# filter-prototype.net
KiCad netlist of a schematic drawn in EAGLE
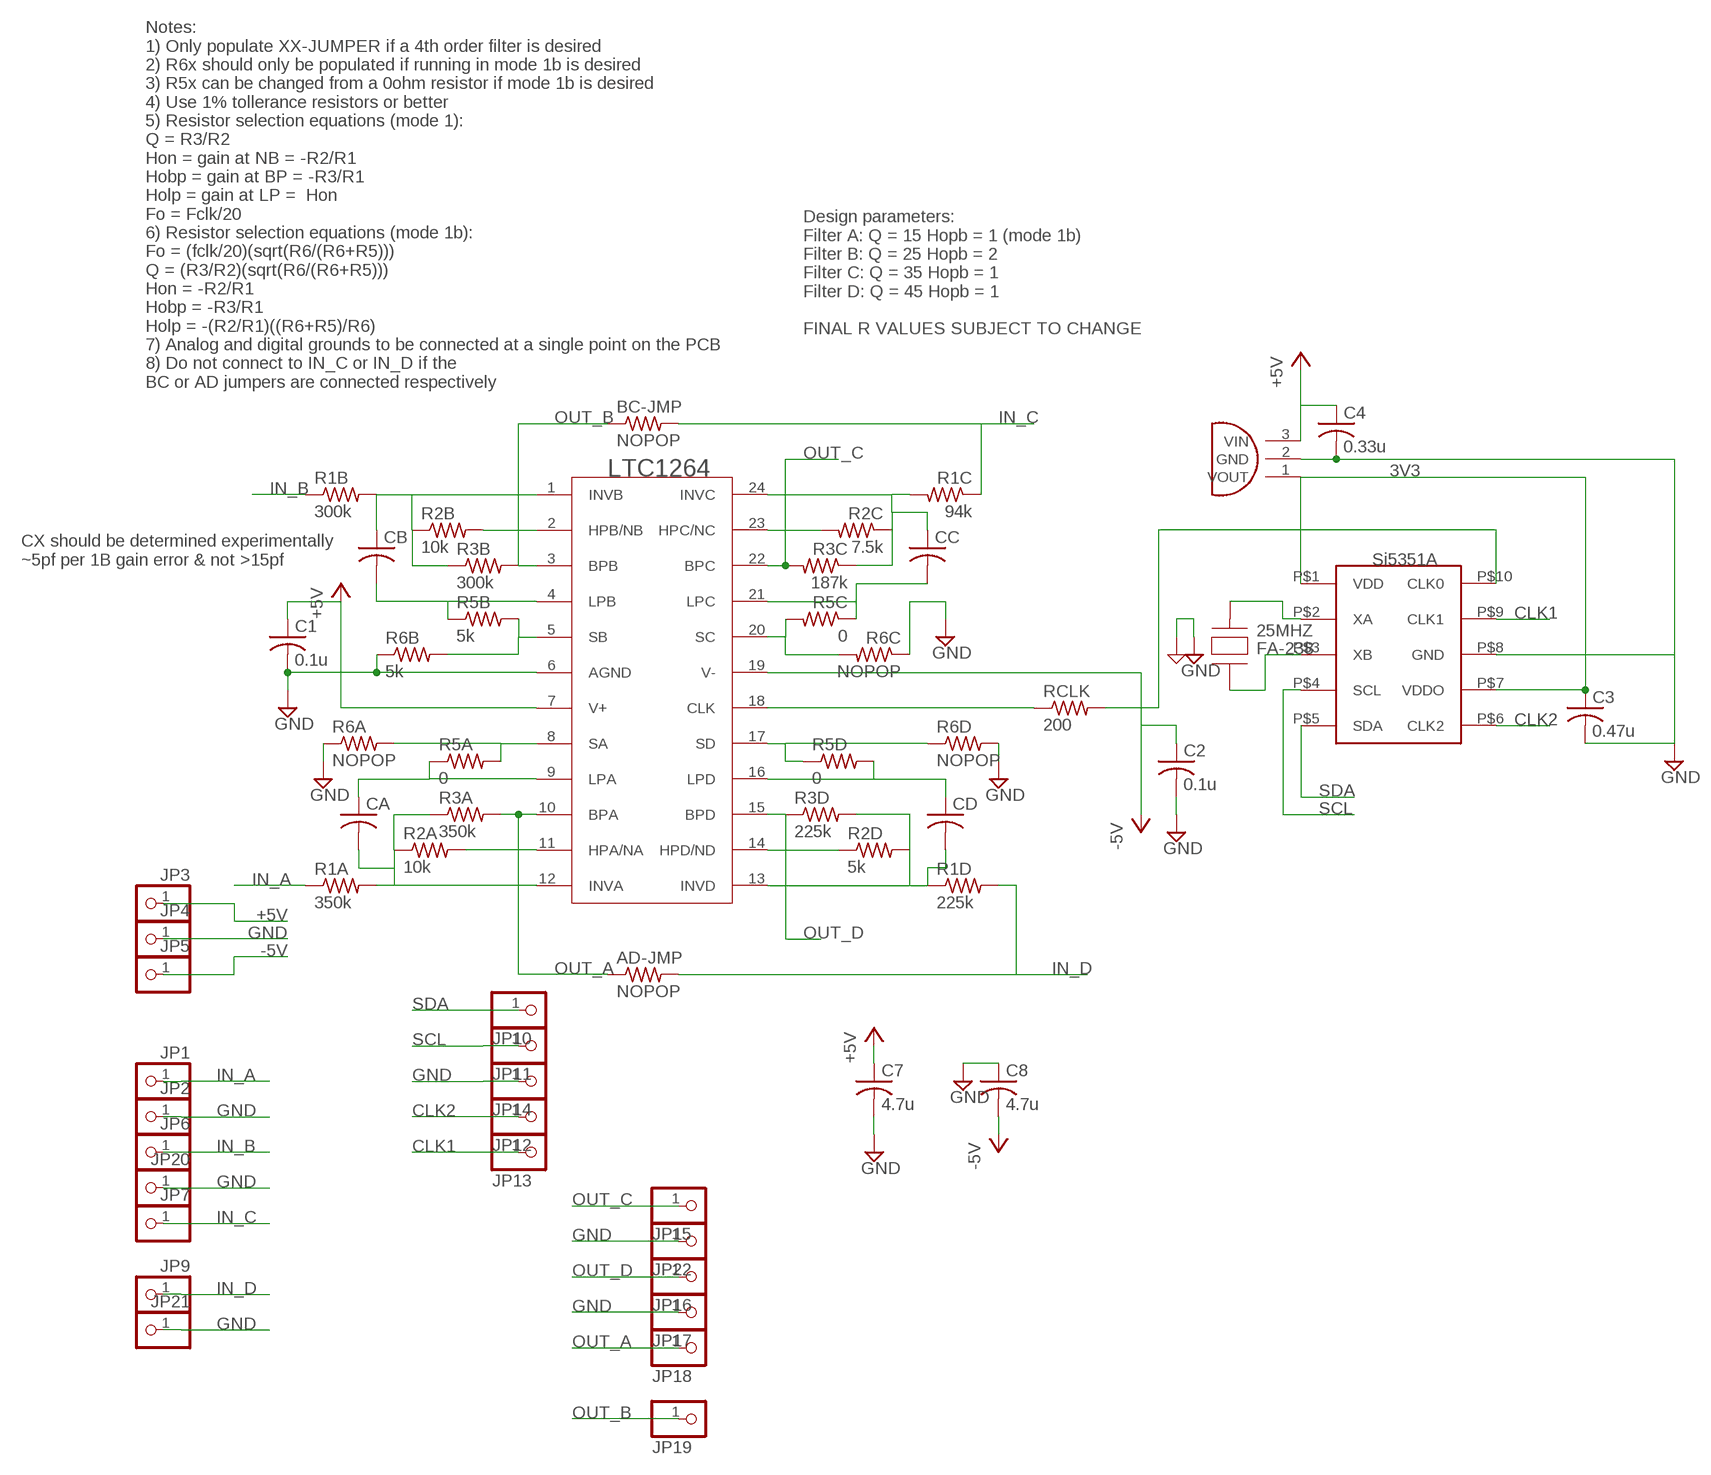
[diagram p0: schematic, sheet 1]

(export (version "E")
  (design (tool "Eeschema 10.0.6"))
  (components
    (comp (ref "25MHZ")
      (value "FA-238")
      (footprint "eagle-import:FA-238")
      (libsource (lib "eagle-import") (part "FA-238"))
    )
    (comp (ref "AD-JMP")
      (value "NOPOP")
      (footprint "eagle-import:R0805")
      (libsource (lib "eagle-import") (part "R-US_R0805"))
    )
    (comp (ref "BC-JMP")
      (value "NOPOP")
      (footprint "eagle-import:R0805")
      (libsource (lib "eagle-import") (part "R-US_R0805"))
    )
    (comp (ref "C1")
      (value "0.1u")
      (footprint "eagle-import:C0805")
      (libsource (lib "eagle-import") (part "C-USC0805"))
    )
    (comp (ref "C2")
      (value "0.1u")
      (footprint "eagle-import:C0805")
      (libsource (lib "eagle-import") (part "C-USC0805"))
    )
    (comp (ref "C3")
      (value "0.47u")
      (footprint "eagle-import:C0805")
      (libsource (lib "eagle-import") (part "C-USC0805"))
    )
    (comp (ref "C4")
      (value "0.33u")
      (footprint "eagle-import:C0805")
      (libsource (lib "eagle-import") (part "C-USC0805"))
    )
    (comp (ref "C7")
      (value "4.7u")
      (footprint "eagle-import:C0805")
      (libsource (lib "eagle-import") (part "C-USC0805"))
    )
    (comp (ref "C8")
      (value "4.7u")
      (footprint "eagle-import:C0805")
      (libsource (lib "eagle-import") (part "C-USC0805"))
    )
    (comp (ref "CA")
      (value "C-USC0805")
      (footprint "eagle-import:C0805")
      (libsource (lib "eagle-import") (part "C-USC0805"))
    )
    (comp (ref "CB")
      (value "C-USC0805")
      (footprint "eagle-import:C0805")
      (libsource (lib "eagle-import") (part "C-USC0805"))
    )
    (comp (ref "CC")
      (value "C-USC0805")
      (footprint "eagle-import:C0805")
      (libsource (lib "eagle-import") (part "C-USC0805"))
    )
    (comp (ref "CD")
      (value "C-USC0805")
      (footprint "eagle-import:C0805")
      (libsource (lib "eagle-import") (part "C-USC0805"))
    )
    (comp (ref "JP1")
      (value "PINHD-1X1")
      (footprint "eagle-import:1X01")
      (libsource (lib "eagle-import") (part "PINHD-1X1"))
    )
    (comp (ref "JP2")
      (value "PINHD-1X1")
      (footprint "eagle-import:1X01")
      (libsource (lib "eagle-import") (part "PINHD-1X1"))
    )
    (comp (ref "JP3")
      (value "PINHD-1X1")
      (footprint "eagle-import:1X01")
      (libsource (lib "eagle-import") (part "PINHD-1X1"))
    )
    (comp (ref "JP4")
      (value "PINHD-1X1")
      (footprint "eagle-import:1X01")
      (libsource (lib "eagle-import") (part "PINHD-1X1"))
    )
    (comp (ref "JP5")
      (value "PINHD-1X1")
      (footprint "eagle-import:1X01")
      (libsource (lib "eagle-import") (part "PINHD-1X1"))
    )
    (comp (ref "JP6")
      (value "PINHD-1X1")
      (footprint "eagle-import:1X01")
      (libsource (lib "eagle-import") (part "PINHD-1X1"))
    )
    (comp (ref "JP7")
      (value "PINHD-1X1")
      (footprint "eagle-import:1X01")
      (libsource (lib "eagle-import") (part "PINHD-1X1"))
    )
    (comp (ref "JP9")
      (value "PINHD-1X1")
      (footprint "eagle-import:1X01")
      (libsource (lib "eagle-import") (part "PINHD-1X1"))
    )
    (comp (ref "JP10")
      (value "PINHD-1X1")
      (footprint "eagle-import:1X01")
      (libsource (lib "eagle-import") (part "PINHD-1X1"))
    )
    (comp (ref "JP11")
      (value "PINHD-1X1")
      (footprint "eagle-import:1X01")
      (libsource (lib "eagle-import") (part "PINHD-1X1"))
    )
    (comp (ref "JP12")
      (value "PINHD-1X1")
      (footprint "eagle-import:1X01")
      (libsource (lib "eagle-import") (part "PINHD-1X1"))
    )
    (comp (ref "JP13")
      (value "PINHD-1X1")
      (footprint "eagle-import:1X01")
      (libsource (lib "eagle-import") (part "PINHD-1X1"))
    )
    (comp (ref "JP14")
      (value "PINHD-1X1")
      (footprint "eagle-import:1X01")
      (libsource (lib "eagle-import") (part "PINHD-1X1"))
    )
    (comp (ref "JP15")
      (value "PINHD-1X1")
      (footprint "eagle-import:1X01")
      (libsource (lib "eagle-import") (part "PINHD-1X1"))
    )
    (comp (ref "JP16")
      (value "PINHD-1X1")
      (footprint "eagle-import:1X01")
      (libsource (lib "eagle-import") (part "PINHD-1X1"))
    )
    (comp (ref "JP17")
      (value "PINHD-1X1")
      (footprint "eagle-import:1X01")
      (libsource (lib "eagle-import") (part "PINHD-1X1"))
    )
    (comp (ref "JP18")
      (value "PINHD-1X1")
      (footprint "eagle-import:1X01")
      (libsource (lib "eagle-import") (part "PINHD-1X1"))
    )
    (comp (ref "JP19")
      (value "PINHD-1X1")
      (footprint "eagle-import:1X01")
      (libsource (lib "eagle-import") (part "PINHD-1X1"))
    )
    (comp (ref "JP20")
      (value "PINHD-1X1")
      (footprint "eagle-import:1X01")
      (libsource (lib "eagle-import") (part "PINHD-1X1"))
    )
    (comp (ref "JP21")
      (value "PINHD-1X1")
      (footprint "eagle-import:1X01")
      (libsource (lib "eagle-import") (part "PINHD-1X1"))
    )
    (comp (ref "JP22")
      (value "PINHD-1X1")
      (footprint "eagle-import:1X01")
      (libsource (lib "eagle-import") (part "PINHD-1X1"))
    )
    (comp (ref "R1A")
      (value "350k")
      (footprint "eagle-import:R0805")
      (libsource (lib "eagle-import") (part "R-US_R0805"))
    )
    (comp (ref "R1B")
      (value "300k")
      (footprint "eagle-import:R0805")
      (libsource (lib "eagle-import") (part "R-US_R0805"))
    )
    (comp (ref "R1C")
      (value "94k")
      (footprint "eagle-import:R0805")
      (libsource (lib "eagle-import") (part "R-US_R0805"))
    )
    (comp (ref "R1D")
      (value "225k")
      (footprint "eagle-import:R0805")
      (libsource (lib "eagle-import") (part "R-US_R0805"))
    )
    (comp (ref "R2A")
      (value "10k")
      (footprint "eagle-import:R0805")
      (libsource (lib "eagle-import") (part "R-US_R0805"))
    )
    (comp (ref "R2B")
      (value "10k")
      (footprint "eagle-import:R0805")
      (libsource (lib "eagle-import") (part "R-US_R0805"))
    )
    (comp (ref "R2C")
      (value "7.5k")
      (footprint "eagle-import:R0805")
      (libsource (lib "eagle-import") (part "R-US_R0805"))
    )
    (comp (ref "R2D")
      (value "5k")
      (footprint "eagle-import:R0805")
      (libsource (lib "eagle-import") (part "R-US_R0805"))
    )
    (comp (ref "R3A")
      (value "350k")
      (footprint "eagle-import:R0805")
      (libsource (lib "eagle-import") (part "R-US_R0805"))
    )
    (comp (ref "R3B")
      (value "300k")
      (footprint "eagle-import:R0805")
      (libsource (lib "eagle-import") (part "R-US_R0805"))
    )
    (comp (ref "R3C")
      (value "187k")
      (footprint "eagle-import:R0805")
      (libsource (lib "eagle-import") (part "R-US_R0805"))
    )
    (comp (ref "R3D")
      (value "225k")
      (footprint "eagle-import:R0805")
      (libsource (lib "eagle-import") (part "R-US_R0805"))
    )
    (comp (ref "R5A")
      (value "0")
      (footprint "eagle-import:R0805")
      (libsource (lib "eagle-import") (part "R-US_R0805"))
    )
    (comp (ref "R5B")
      (value "5k")
      (footprint "eagle-import:R0805")
      (libsource (lib "eagle-import") (part "R-US_R0805"))
    )
    (comp (ref "R5C")
      (value "0")
      (footprint "eagle-import:R0805")
      (libsource (lib "eagle-import") (part "R-US_R0805"))
    )
    (comp (ref "R5D")
      (value "0")
      (footprint "eagle-import:R0805")
      (libsource (lib "eagle-import") (part "R-US_R0805"))
    )
    (comp (ref "R6A")
      (value "NOPOP")
      (footprint "eagle-import:R0805")
      (libsource (lib "eagle-import") (part "R-US_R0805"))
    )
    (comp (ref "R6B")
      (value "5k")
      (footprint "eagle-import:R0805")
      (libsource (lib "eagle-import") (part "R-US_R0805"))
    )
    (comp (ref "R6C")
      (value "NOPOP")
      (footprint "eagle-import:R0805")
      (libsource (lib "eagle-import") (part "R-US_R0805"))
    )
    (comp (ref "R6D")
      (value "NOPOP")
      (footprint "eagle-import:R0805")
      (libsource (lib "eagle-import") (part "R-US_R0805"))
    )
    (comp (ref "RCLK")
      (value "200")
      (footprint "eagle-import:R0805")
      (libsource (lib "eagle-import") (part "R-US_R0805"))
    )
    (comp (ref "U$1")
      (value "LTC1264SMD")
      (footprint "eagle-import:SO24W")
      (libsource (lib "eagle-import") (part "LTC1264SMD"))
    )
    (comp (ref "U$2")
      (value "SI5351A")
      (footprint "eagle-import:MSOP-10")
      (libsource (lib "eagle-import") (part "SI5351A"))
    )
    (comp (ref "U$3")
      (value "L78L33ACZ")
      (footprint "eagle-import:TO-92")
      (libsource (lib "eagle-import") (part "L78L33ACZ"))
    )
  )
  (nets
    (net (code "1") (name "+5V") (class "Default")
      (node (ref "C1") (pin "1") (pinfunction "1_1") (pintype "passive"))
      (node (ref "C4") (pin "1") (pinfunction "1_1") (pintype "passive"))
      (node (ref "C7") (pin "1") (pinfunction "1_1") (pintype "passive"))
      (node (ref "JP3") (pin "1") (pinfunction "1_1") (pintype "passive"))
      (node (ref "U$1") (pin "7") (pinfunction "V+_7") (pintype "bidirectional"))
      (node (ref "U$3") (pin "3") (pinfunction "VIN_3") (pintype "bidirectional"))
    )
    (net (code "2") (name "-5V") (class "Default")
      (node (ref "C2") (pin "1") (pinfunction "1_1") (pintype "passive"))
      (node (ref "C8") (pin "2") (pinfunction "2_2") (pintype "passive"))
      (node (ref "JP5") (pin "1") (pinfunction "1_1") (pintype "passive"))
      (node (ref "U$1") (pin "19") (pinfunction "V-_19") (pintype "bidirectional"))
    )
    (net (code "3") (name "/3V3") (class "Default")
      (node (ref "C3") (pin "1") (pinfunction "1_1") (pintype "passive"))
      (node (ref "U$2") (pin "P$1") (pinfunction "VDD_P$1") (pintype "bidirectional"))
      (node (ref "U$2") (pin "P$7") (pinfunction "VDDO_P$7") (pintype "bidirectional"))
      (node (ref "U$3") (pin "1") (pinfunction "VOUT_1") (pintype "bidirectional"))
    )
    (net (code "4") (name "/CLK1") (class "Default")
      (node (ref "JP13") (pin "1") (pinfunction "1_1") (pintype "passive"))
      (node (ref "U$2") (pin "P$9") (pinfunction "CLK1_P$9") (pintype "bidirectional"))
    )
    (net (code "5") (name "/CLK2") (class "Default")
      (node (ref "JP12") (pin "1") (pinfunction "1_1") (pintype "passive"))
      (node (ref "U$2") (pin "P$6") (pinfunction "CLK2_P$6") (pintype "bidirectional"))
    )
    (net (code "6") (name "/IN_A") (class "Default")
      (node (ref "JP1") (pin "1") (pinfunction "1_1") (pintype "passive"))
      (node (ref "R1A") (pin "1") (pinfunction "1_1") (pintype "passive"))
    )
    (net (code "7") (name "/IN_B") (class "Default")
      (node (ref "JP6") (pin "1") (pinfunction "1_1") (pintype "passive"))
      (node (ref "R1B") (pin "1") (pinfunction "1_1") (pintype "passive"))
    )
    (net (code "8") (name "/IN_C") (class "Default")
      (node (ref "BC-JMP") (pin "2") (pinfunction "2_2") (pintype "passive"))
      (node (ref "JP7") (pin "1") (pinfunction "1_1") (pintype "passive"))
      (node (ref "R1C") (pin "1") (pinfunction "1_1") (pintype "passive"))
    )
    (net (code "9") (name "/IN_D") (class "Default")
      (node (ref "AD-JMP") (pin "2") (pinfunction "2_2") (pintype "passive"))
      (node (ref "JP9") (pin "1") (pinfunction "1_1") (pintype "passive"))
      (node (ref "R1D") (pin "2") (pinfunction "2_2") (pintype "passive"))
    )
    (net (code "10") (name "/OUT_A") (class "Default")
      (node (ref "AD-JMP") (pin "1") (pinfunction "1_1") (pintype "passive"))
      (node (ref "JP18") (pin "1") (pinfunction "1_1") (pintype "passive"))
      (node (ref "R3A") (pin "2") (pinfunction "2_2") (pintype "passive"))
      (node (ref "U$1") (pin "10") (pinfunction "BPA_10") (pintype "bidirectional"))
    )
    (net (code "11") (name "/OUT_B") (class "Default")
      (node (ref "BC-JMP") (pin "1") (pinfunction "1_1") (pintype "passive"))
      (node (ref "JP19") (pin "1") (pinfunction "1_1") (pintype "passive"))
      (node (ref "R3B") (pin "2") (pinfunction "2_2") (pintype "passive"))
      (node (ref "U$1") (pin "3") (pinfunction "BPB_3") (pintype "bidirectional"))
    )
    (net (code "12") (name "/OUT_C") (class "Default")
      (node (ref "JP15") (pin "1") (pinfunction "1_1") (pintype "passive"))
      (node (ref "R3C") (pin "2") (pinfunction "2_2") (pintype "passive"))
      (node (ref "U$1") (pin "22") (pinfunction "BPC_22") (pintype "bidirectional"))
    )
    (net (code "13") (name "/OUT_D") (class "Default")
      (node (ref "JP16") (pin "1") (pinfunction "1_1") (pintype "passive"))
      (node (ref "R3D") (pin "1") (pinfunction "1_1") (pintype "passive"))
      (node (ref "U$1") (pin "15") (pinfunction "BPD_15") (pintype "bidirectional"))
    )
    (net (code "14") (name "/SCL") (class "Default")
      (node (ref "JP11") (pin "1") (pinfunction "1_1") (pintype "passive"))
      (node (ref "U$2") (pin "P$4") (pinfunction "SCL_P$4") (pintype "bidirectional"))
    )
    (net (code "15") (name "/SDA") (class "Default")
      (node (ref "JP10") (pin "1") (pinfunction "1_1") (pintype "passive"))
      (node (ref "U$2") (pin "P$5") (pinfunction "SDA_P$5") (pintype "bidirectional"))
    )
    (net (code "16") (name "GND") (class "Default")
      (node (ref "25MHZ") (pin "P$1") (pinfunction "GND_P$1") (pintype "bidirectional"))
      (node (ref "25MHZ") (pin "P$3") (pinfunction "GND_P$3") (pintype "bidirectional"))
      (node (ref "C1") (pin "2") (pinfunction "2_2") (pintype "passive"))
      (node (ref "C2") (pin "2") (pinfunction "2_2") (pintype "passive"))
      (node (ref "C3") (pin "2") (pinfunction "2_2") (pintype "passive"))
      (node (ref "C4") (pin "2") (pinfunction "2_2") (pintype "passive"))
      (node (ref "C7") (pin "2") (pinfunction "2_2") (pintype "passive"))
      (node (ref "C8") (pin "1") (pinfunction "1_1") (pintype "passive"))
      (node (ref "JP14") (pin "1") (pinfunction "1_1") (pintype "passive"))
      (node (ref "JP17") (pin "1") (pinfunction "1_1") (pintype "passive"))
      (node (ref "JP2") (pin "1") (pinfunction "1_1") (pintype "passive"))
      (node (ref "JP20") (pin "1") (pinfunction "1_1") (pintype "passive"))
      (node (ref "JP21") (pin "1") (pinfunction "1_1") (pintype "passive"))
      (node (ref "JP22") (pin "1") (pinfunction "1_1") (pintype "passive"))
      (node (ref "JP4") (pin "1") (pinfunction "1_1") (pintype "passive"))
      (node (ref "R6A") (pin "1") (pinfunction "1_1") (pintype "passive"))
      (node (ref "R6B") (pin "1") (pinfunction "1_1") (pintype "passive"))
      (node (ref "R6C") (pin "1") (pinfunction "1_1") (pintype "passive"))
      (node (ref "R6D") (pin "2") (pinfunction "2_2") (pintype "passive"))
      (node (ref "U$1") (pin "6") (pinfunction "AGND_6") (pintype "bidirectional"))
      (node (ref "U$2") (pin "P$8") (pinfunction "GND_P$8") (pintype "bidirectional"))
      (node (ref "U$3") (pin "2") (pinfunction "GND_2") (pintype "bidirectional"))
    )
    (net (code "17") (name "Net-(25MHZ-XA)") (class "Default")
      (node (ref "25MHZ") (pin "P$4") (pinfunction "XA_P$4") (pintype "bidirectional"))
      (node (ref "U$2") (pin "P$2") (pinfunction "XA_P$2") (pintype "bidirectional"))
    )
    (net (code "18") (name "Net-(25MHZ-XB)") (class "Default")
      (node (ref "25MHZ") (pin "P$2") (pinfunction "XB_P$2") (pintype "bidirectional"))
      (node (ref "U$2") (pin "P$3") (pinfunction "XB_P$3") (pintype "bidirectional"))
    )
    (net (code "19") (name "Net-(U$1-CLK)") (class "Default")
      (node (ref "RCLK") (pin "1") (pinfunction "1_1") (pintype "passive"))
      (node (ref "U$1") (pin "18") (pinfunction "CLK_18") (pintype "bidirectional"))
    )
    (net (code "20") (name "Net-(U$1-HPA{slash}NA)") (class "Default")
      (node (ref "R2A") (pin "2") (pinfunction "2_2") (pintype "passive"))
      (node (ref "U$1") (pin "11") (pinfunction "HPA/NA_11") (pintype "bidirectional"))
    )
    (net (code "21") (name "Net-(U$1-HPB{slash}NB)") (class "Default")
      (node (ref "R2B") (pin "2") (pinfunction "2_2") (pintype "passive"))
      (node (ref "U$1") (pin "2") (pinfunction "HPB/NB_2") (pintype "bidirectional"))
    )
    (net (code "22") (name "Net-(U$1-HPC{slash}NC)") (class "Default")
      (node (ref "R2C") (pin "2") (pinfunction "2_2") (pintype "passive"))
      (node (ref "U$1") (pin "23") (pinfunction "HPC/NC_23") (pintype "bidirectional"))
    )
    (net (code "23") (name "Net-(U$1-HPD{slash}ND)") (class "Default")
      (node (ref "R2D") (pin "1") (pinfunction "1_1") (pintype "passive"))
      (node (ref "U$1") (pin "14") (pinfunction "HPD/ND_14") (pintype "bidirectional"))
    )
    (net (code "24") (name "Net-(U$1-INVA)") (class "Default")
      (node (ref "CA") (pin "2") (pinfunction "2_2") (pintype "passive"))
      (node (ref "R1A") (pin "2") (pinfunction "2_2") (pintype "passive"))
      (node (ref "R2A") (pin "1") (pinfunction "1_1") (pintype "passive"))
      (node (ref "R3A") (pin "1") (pinfunction "1_1") (pintype "passive"))
      (node (ref "U$1") (pin "12") (pinfunction "INVA_12") (pintype "bidirectional"))
    )
    (net (code "25") (name "Net-(U$1-INVB)") (class "Default")
      (node (ref "CB") (pin "1") (pinfunction "1_1") (pintype "passive"))
      (node (ref "R1B") (pin "2") (pinfunction "2_2") (pintype "passive"))
      (node (ref "R2B") (pin "1") (pinfunction "1_1") (pintype "passive"))
      (node (ref "R3B") (pin "1") (pinfunction "1_1") (pintype "passive"))
      (node (ref "U$1") (pin "1") (pinfunction "INVB_1") (pintype "bidirectional"))
    )
    (net (code "26") (name "Net-(U$1-INVC)") (class "Default")
      (node (ref "CC") (pin "1") (pinfunction "1_1") (pintype "passive"))
      (node (ref "R1C") (pin "2") (pinfunction "2_2") (pintype "passive"))
      (node (ref "R2C") (pin "1") (pinfunction "1_1") (pintype "passive"))
      (node (ref "R3C") (pin "1") (pinfunction "1_1") (pintype "passive"))
      (node (ref "U$1") (pin "24") (pinfunction "INVC_24") (pintype "bidirectional"))
    )
    (net (code "27") (name "Net-(U$1-INVD)") (class "Default")
      (node (ref "CD") (pin "2") (pinfunction "2_2") (pintype "passive"))
      (node (ref "R1D") (pin "1") (pinfunction "1_1") (pintype "passive"))
      (node (ref "R2D") (pin "2") (pinfunction "2_2") (pintype "passive"))
      (node (ref "R3D") (pin "2") (pinfunction "2_2") (pintype "passive"))
      (node (ref "U$1") (pin "13") (pinfunction "INVD_13") (pintype "bidirectional"))
    )
    (net (code "28") (name "Net-(U$1-LPA)") (class "Default")
      (node (ref "CA") (pin "1") (pinfunction "1_1") (pintype "passive"))
      (node (ref "R5A") (pin "1") (pinfunction "1_1") (pintype "passive"))
      (node (ref "U$1") (pin "9") (pinfunction "LPA_9") (pintype "bidirectional"))
    )
    (net (code "29") (name "Net-(U$1-LPB)") (class "Default")
      (node (ref "CB") (pin "2") (pinfunction "2_2") (pintype "passive"))
      (node (ref "R5B") (pin "1") (pinfunction "1_1") (pintype "passive"))
      (node (ref "U$1") (pin "4") (pinfunction "LPB_4") (pintype "bidirectional"))
    )
    (net (code "30") (name "Net-(U$1-LPC)") (class "Default")
      (node (ref "CC") (pin "2") (pinfunction "2_2") (pintype "passive"))
      (node (ref "R5C") (pin "1") (pinfunction "1_1") (pintype "passive"))
      (node (ref "U$1") (pin "21") (pinfunction "LPC_21") (pintype "bidirectional"))
    )
    (net (code "31") (name "Net-(U$1-LPD)") (class "Default")
      (node (ref "CD") (pin "1") (pinfunction "1_1") (pintype "passive"))
      (node (ref "R5D") (pin "2") (pinfunction "2_2") (pintype "passive"))
      (node (ref "U$1") (pin "16") (pinfunction "LPD_16") (pintype "bidirectional"))
    )
    (net (code "32") (name "Net-(U$1-SA)") (class "Default")
      (node (ref "R5A") (pin "2") (pinfunction "2_2") (pintype "passive"))
      (node (ref "R6A") (pin "2") (pinfunction "2_2") (pintype "passive"))
      (node (ref "U$1") (pin "8") (pinfunction "SA_8") (pintype "bidirectional"))
    )
    (net (code "33") (name "Net-(U$1-SB)") (class "Default")
      (node (ref "R5B") (pin "2") (pinfunction "2_2") (pintype "passive"))
      (node (ref "R6B") (pin "2") (pinfunction "2_2") (pintype "passive"))
      (node (ref "U$1") (pin "5") (pinfunction "SB_5") (pintype "bidirectional"))
    )
    (net (code "34") (name "Net-(U$1-SC)") (class "Default")
      (node (ref "R5C") (pin "2") (pinfunction "2_2") (pintype "passive"))
      (node (ref "R6C") (pin "2") (pinfunction "2_2") (pintype "passive"))
      (node (ref "U$1") (pin "20") (pinfunction "SC_20") (pintype "bidirectional"))
    )
    (net (code "35") (name "Net-(U$1-SD)") (class "Default")
      (node (ref "R5D") (pin "1") (pinfunction "1_1") (pintype "passive"))
      (node (ref "R6D") (pin "1") (pinfunction "1_1") (pintype "passive"))
      (node (ref "U$1") (pin "17") (pinfunction "SD_17") (pintype "bidirectional"))
    )
    (net (code "36") (name "Net-(U$2-CLK0)") (class "Default")
      (node (ref "RCLK") (pin "2") (pinfunction "2_2") (pintype "passive"))
      (node (ref "U$2") (pin "P$10") (pinfunction "CLK0_P$10") (pintype "bidirectional"))
    )
  )
)
